# adafruit_flora_mainboard.net
KiCad netlist of a schematic drawn in EAGLE
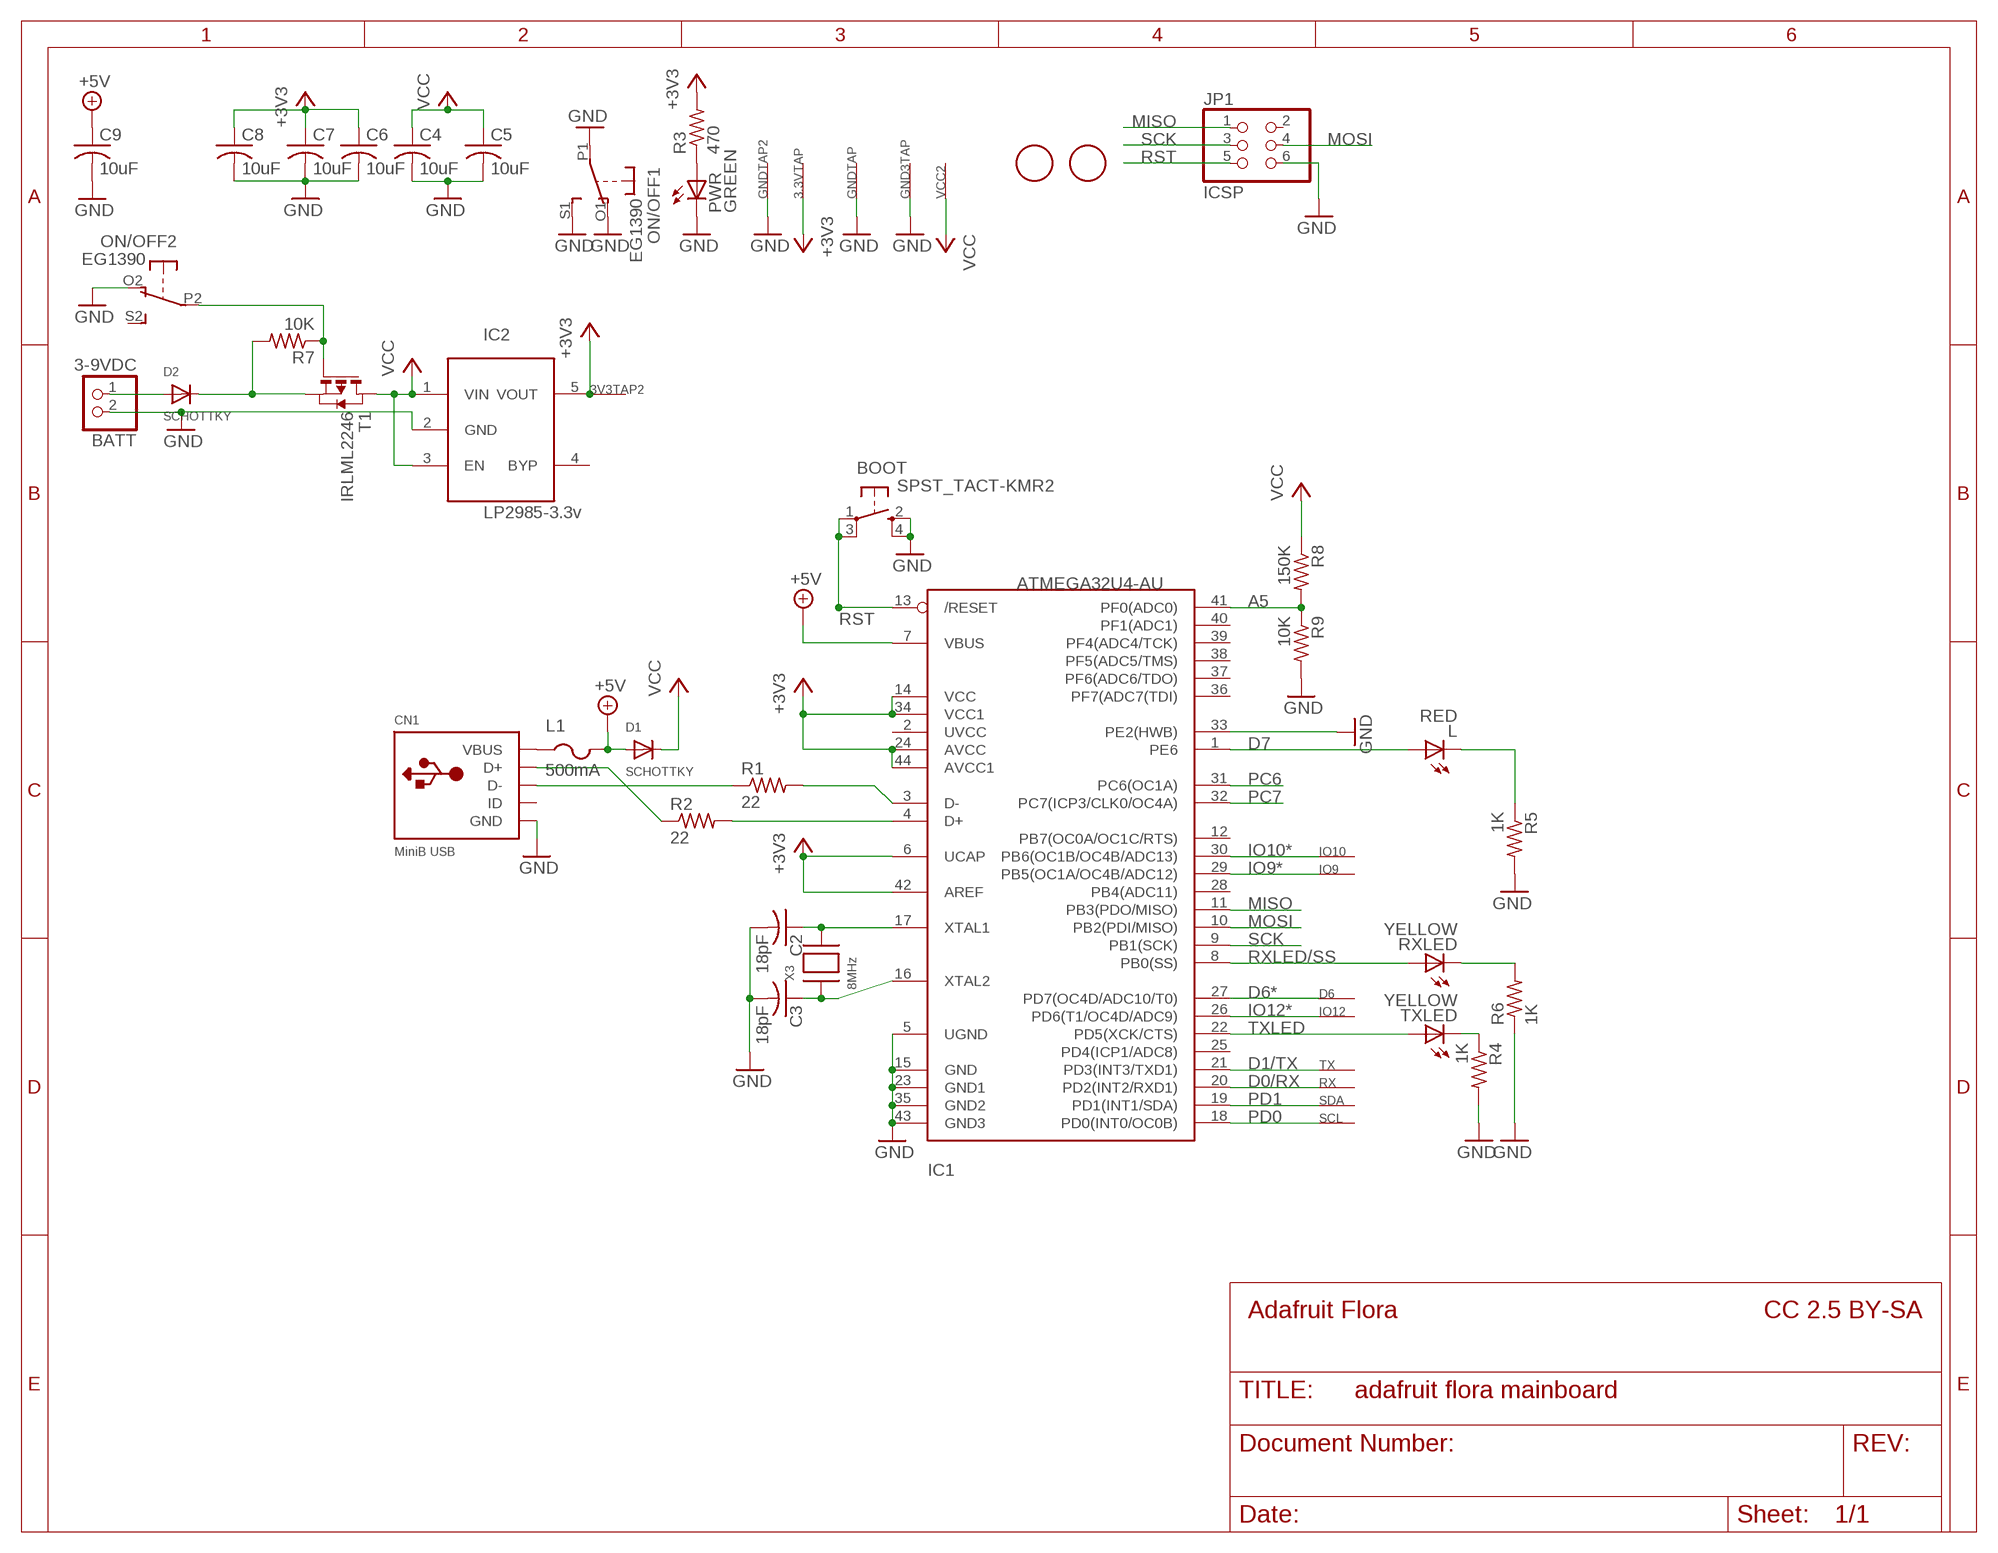
[diagram p0: schematic, sheet 1]

(export (version "E")
  (design (tool "Eeschema 10.0.6"))
  (components
    (comp (ref "3.3VTAP")
      (value "SEWTAP-2.0IN")
      (footprint "eagle-import:SEWINGTAP_2.0")
      (libsource (lib "eagle-import") (part "SEWTAP-2.0IN"))
    )
    (comp (ref "3V3TAP2")
      (value "SEWTAP-2.0IN")
      (footprint "eagle-import:SEWINGTAP_2.0")
      (libsource (lib "eagle-import") (part "SEWTAP-2.0IN"))
    )
    (comp (ref "BATT")
      (value "3-9VDC")
      (footprint "eagle-import:JST-PH-2-SMT-RA")
      (libsource (lib "eagle-import") (part "JST_2PIN-SMT-RA"))
    )
    (comp (ref "BOOT")
      (value "SPST_TACT-KMR2")
      (footprint "eagle-import:KMR2")
      (libsource (lib "eagle-import") (part "SPST_TACT-KMR2"))
    )
    (comp (ref "C2")
      (value "18pF")
      (footprint "eagle-import:C0805K")
      (libsource (lib "eagle-import") (part "C-USC0805K"))
    )
    (comp (ref "C3")
      (value "18pF")
      (footprint "eagle-import:C0805K")
      (libsource (lib "eagle-import") (part "C-USC0805K"))
    )
    (comp (ref "C4")
      (value "10uF")
      (footprint "eagle-import:C0805K")
      (libsource (lib "eagle-import") (part "C-USC0805K"))
    )
    (comp (ref "C5")
      (value "10uF")
      (footprint "eagle-import:C0805K")
      (libsource (lib "eagle-import") (part "C-USC0805K"))
    )
    (comp (ref "C6")
      (value "10uF")
      (footprint "eagle-import:C0805K")
      (libsource (lib "eagle-import") (part "C-USC0805K"))
    )
    (comp (ref "C7")
      (value "10uF")
      (footprint "eagle-import:C0805K")
      (libsource (lib "eagle-import") (part "C-USC0805K"))
    )
    (comp (ref "C8")
      (value "10uF")
      (footprint "eagle-import:C0805K")
      (libsource (lib "eagle-import") (part "C-USC0805K"))
    )
    (comp (ref "C9")
      (value "10uF")
      (footprint "eagle-import:C0805K")
      (libsource (lib "eagle-import") (part "C-USC0805K"))
    )
    (comp (ref "CN1")
      (value "MiniB USB")
      (footprint "eagle-import:USB-MINIB_LARGER")
      (libsource (lib "eagle-import") (part "USBMINIBLARGE"))
    )
    (comp (ref "D1")
      (value "SCHOTTKY")
      (footprint "eagle-import:SOD-123")
      (libsource (lib "eagle-import") (part "DIODESOD-123"))
    )
    (comp (ref "D2")
      (value "SCHOTTKY")
      (footprint "eagle-import:SOD-123")
      (libsource (lib "eagle-import") (part "DIODESOD-123"))
    )
    (comp (ref "D6")
      (value "SEWTAP-2.0IN")
      (footprint "eagle-import:SEWINGTAP_2.0")
      (libsource (lib "eagle-import") (part "SEWTAP-2.0IN"))
    )
    (comp (ref "GND3TAP")
      (value "SEWTAP-2.0IN")
      (footprint "eagle-import:SEWINGTAP_2.0")
      (libsource (lib "eagle-import") (part "SEWTAP-2.0IN"))
    )
    (comp (ref "GNDTAP")
      (value "SEWTAP-2.0IN")
      (footprint "eagle-import:SEWINGTAP_2.0")
      (libsource (lib "eagle-import") (part "SEWTAP-2.0IN"))
    )
    (comp (ref "GNDTAP2")
      (value "SEWTAP-2.0IN")
      (footprint "eagle-import:SEWINGTAP_2.0")
      (libsource (lib "eagle-import") (part "SEWTAP-2.0IN"))
    )
    (comp (ref "IC1")
      (value "ATMEGA32U4-AU")
      (footprint "eagle-import:TQFP44")
      (libsource (lib "eagle-import") (part "ATMEGA32U4-AU"))
    )
    (comp (ref "IC2")
      (value "LP2985-3.3v")
      (footprint "eagle-import:SOT23-5L")
      (libsource (lib "eagle-import") (part "LP298XS"))
    )
    (comp (ref "IO9")
      (value "SEWTAP-2.0IN")
      (footprint "eagle-import:SEWINGTAP_2.0")
      (libsource (lib "eagle-import") (part "SEWTAP-2.0IN"))
    )
    (comp (ref "IO10")
      (value "SEWTAP-2.0IN")
      (footprint "eagle-import:SEWINGTAP_2.0")
      (libsource (lib "eagle-import") (part "SEWTAP-2.0IN"))
    )
    (comp (ref "IO12")
      (value "SEWTAP-2.0IN")
      (footprint "eagle-import:SEWINGTAP_2.0")
      (libsource (lib "eagle-import") (part "SEWTAP-2.0IN"))
    )
    (comp (ref "JP1")
      (value "ICSP")
      (footprint "eagle-import:2X03")
      (libsource (lib "eagle-import") (part "PINHD-2X3"))
    )
    (comp (ref "L")
      (value "RED")
      (footprint "eagle-import:CHIPLED_0805")
      (libsource (lib "eagle-import") (part "LEDCHIPLED_0805"))
    )
    (comp (ref "L1")
      (value "500mA")
      (footprint "eagle-import:R1206")
      (libsource (lib "eagle-import") (part "PTCFUSE-1206"))
    )
    (comp (ref "ON/OFF")
      (value "EG1390")
      (footprint "eagle-import:EG1390")
      (libsource (lib "eagle-import") (part "DPDT-EG1390"))
    )
    (comp (ref "PWR")
      (value "GREEN")
      (footprint "eagle-import:CHIPLED_0805")
      (libsource (lib "eagle-import") (part "LEDCHIPLED_0805"))
    )
    (comp (ref "R1")
      (value "22")
      (footprint "eagle-import:R0805")
      (libsource (lib "eagle-import") (part "R-US_R0805"))
    )
    (comp (ref "R2")
      (value "22")
      (footprint "eagle-import:R0805")
      (libsource (lib "eagle-import") (part "R-US_R0805"))
    )
    (comp (ref "R3")
      (value "470")
      (footprint "eagle-import:R0805")
      (libsource (lib "eagle-import") (part "R-US_R0805"))
    )
    (comp (ref "R4")
      (value "1K")
      (footprint "eagle-import:R0805")
      (libsource (lib "eagle-import") (part "R-US_R0805"))
    )
    (comp (ref "R5")
      (value "1K")
      (footprint "eagle-import:R0805")
      (libsource (lib "eagle-import") (part "R-US_R0805"))
    )
    (comp (ref "R6")
      (value "1K")
      (footprint "eagle-import:R0805")
      (libsource (lib "eagle-import") (part "R-US_R0805"))
    )
    (comp (ref "R7")
      (value "10K")
      (footprint "eagle-import:R0805")
      (libsource (lib "eagle-import") (part "R-US_R0805"))
    )
    (comp (ref "R8")
      (value "150K")
      (footprint "eagle-import:R0805")
      (libsource (lib "eagle-import") (part "R-US_R0805"))
    )
    (comp (ref "R9")
      (value "10K")
      (footprint "eagle-import:R0805")
      (libsource (lib "eagle-import") (part "R-US_R0805"))
    )
    (comp (ref "RX")
      (value "SEWTAP-2.0IN")
      (footprint "eagle-import:SEWINGTAP_2.0")
      (libsource (lib "eagle-import") (part "SEWTAP-2.0IN"))
    )
    (comp (ref "RXLED")
      (value "YELLOW")
      (footprint "eagle-import:CHIPLED_0805")
      (libsource (lib "eagle-import") (part "LEDCHIPLED_0805"))
    )
    (comp (ref "SCL")
      (value "SEWTAP-2.0IN")
      (footprint "eagle-import:SEWINGTAP_2.0")
      (libsource (lib "eagle-import") (part "SEWTAP-2.0IN"))
    )
    (comp (ref "SDA")
      (value "SEWTAP-2.0IN")
      (footprint "eagle-import:SEWINGTAP_2.0")
      (libsource (lib "eagle-import") (part "SEWTAP-2.0IN"))
    )
    (comp (ref "T1")
      (value "IRLML2246")
      (footprint "eagle-import:SOT-23")
      (libsource (lib "eagle-import") (part "PMOSSOT23"))
    )
    (comp (ref "TX")
      (value "SEWTAP-2.0IN")
      (footprint "eagle-import:SEWINGTAP_2.0")
      (libsource (lib "eagle-import") (part "SEWTAP-2.0IN"))
    )
    (comp (ref "TXLED")
      (value "YELLOW")
      (footprint "eagle-import:CHIPLED_0805")
      (libsource (lib "eagle-import") (part "LEDCHIPLED_0805"))
    )
    (comp (ref "U$2")
      (value "FIDUCIAL")
      (footprint "eagle-import:FIDUCIAL_1MM")
      (libsource (lib "eagle-import") (part "FIDUCIAL"))
    )
    (comp (ref "U$6")
      (value "FIDUCIAL")
      (footprint "eagle-import:FIDUCIAL_1MM")
      (libsource (lib "eagle-import") (part "FIDUCIAL"))
    )
    (comp (ref "VCC2")
      (value "SEWTAP-2.0IN")
      (footprint "eagle-import:SEWINGTAP_2.0")
      (libsource (lib "eagle-import") (part "SEWTAP-2.0IN"))
    )
    (comp (ref "X3")
      (value "8MHz")
      (footprint "eagle-import:NX5032")
      (libsource (lib "eagle-import") (part "XTALNX5032"))
    )
  )
  (nets
    (net (code "1") (name "+3V3") (class "Default")
      (node (ref "3.3VTAP") (pin "P$1") (pinfunction "SEW_P$1") (pintype "bidirectional"))
      (node (ref "3V3TAP2") (pin "P$1") (pinfunction "SEW_P$1") (pintype "bidirectional"))
      (node (ref "C6") (pin "1") (pinfunction "1_1") (pintype "passive"))
      (node (ref "C7") (pin "1") (pinfunction "1_1") (pintype "passive"))
      (node (ref "C8") (pin "1") (pinfunction "1_1") (pintype "passive"))
      (node (ref "IC1") (pin "14") (pinfunction "VCC_14") (pintype "bidirectional"))
      (node (ref "IC1") (pin "24") (pinfunction "AVCC_24") (pintype "bidirectional"))
      (node (ref "IC1") (pin "34") (pinfunction "VCC1_34") (pintype "bidirectional"))
      (node (ref "IC1") (pin "42") (pinfunction "AREF_42") (pintype "bidirectional"))
      (node (ref "IC1") (pin "44") (pinfunction "AVCC1_44") (pintype "bidirectional"))
      (node (ref "IC1") (pin "6") (pinfunction "UCAP_6") (pintype "bidirectional"))
      (node (ref "IC2") (pin "5") (pinfunction "VOUT_5") (pintype "bidirectional"))
      (node (ref "R3") (pin "2") (pinfunction "2_2") (pintype "passive"))
    )
    (net (code "2") (name "+5V") (class "Default")
      (node (ref "C9") (pin "1") (pinfunction "1_1") (pintype "passive"))
      (node (ref "D1") (pin "A") (pinfunction "A_A") (pintype "passive"))
      (node (ref "IC1") (pin "7") (pinfunction "VBUS_7") (pintype "bidirectional"))
      (node (ref "L1") (pin "2") (pinfunction "2_2") (pintype "passive"))
    )
    (net (code "3") (name "/A5") (class "Default")
      (node (ref "IC1") (pin "41") (pinfunction "PF0(ADC0)_41") (pintype "bidirectional"))
      (node (ref "R8") (pin "2") (pinfunction "2_2") (pintype "passive"))
      (node (ref "R9") (pin "1") (pinfunction "1_1") (pintype "passive"))
    )
    (net (code "4") (name "/D0{slash}RX") (class "Default")
      (node (ref "IC1") (pin "20") (pinfunction "PD2(INT2/RXD1)_20") (pintype "bidirectional"))
      (node (ref "RX") (pin "P$1") (pinfunction "SEW_P$1") (pintype "bidirectional"))
    )
    (net (code "5") (name "/D1{slash}TX") (class "Default")
      (node (ref "IC1") (pin "21") (pinfunction "PD3(INT3/TXD1)_21") (pintype "bidirectional"))
      (node (ref "TX") (pin "P$1") (pinfunction "SEW_P$1") (pintype "bidirectional"))
    )
    (net (code "6") (name "/D6*") (class "Default")
      (node (ref "D6") (pin "P$1") (pinfunction "SEW_P$1") (pintype "bidirectional"))
      (node (ref "IC1") (pin "27") (pinfunction "PD7(OC4D/ADC10/T0)_27") (pintype "bidirectional"))
    )
    (net (code "7") (name "/D7") (class "Default")
      (node (ref "IC1") (pin "1") (pinfunction "PE6_1") (pintype "bidirectional"))
      (node (ref "L") (pin "A") (pinfunction "A_A") (pintype "passive"))
    )
    (net (code "8") (name "/IO9*") (class "Default")
      (node (ref "IC1") (pin "29") (pinfunction "PB5(OC1A/OC4B/ADC12)_29") (pintype "bidirectional"))
      (node (ref "IO9") (pin "P$1") (pinfunction "SEW_P$1") (pintype "bidirectional"))
    )
    (net (code "9") (name "/IO10*") (class "Default")
      (node (ref "IC1") (pin "30") (pinfunction "PB6(OC1B/OC4B/ADC13)_30") (pintype "bidirectional"))
      (node (ref "IO10") (pin "P$1") (pinfunction "SEW_P$1") (pintype "bidirectional"))
    )
    (net (code "10") (name "/IO12*") (class "Default")
      (node (ref "IC1") (pin "26") (pinfunction "PD6(T1/OC4D/ADC9)_26") (pintype "bidirectional"))
      (node (ref "IO12") (pin "P$1") (pinfunction "SEW_P$1") (pintype "bidirectional"))
    )
    (net (code "11") (name "/MISO") (class "Default")
      (node (ref "IC1") (pin "11") (pinfunction "PB3(PDO/MISO)_11") (pintype "bidirectional"))
      (node (ref "JP1") (pin "1") (pinfunction "1_1") (pintype "passive"))
    )
    (net (code "12") (name "/MOSI") (class "Default")
      (node (ref "IC1") (pin "10") (pinfunction "PB2(PDI/MISO)_10") (pintype "bidirectional"))
      (node (ref "JP1") (pin "4") (pinfunction "4_4") (pintype "passive"))
    )
    (net (code "13") (name "/PC6") (class "Default")
      (node (ref "IC1") (pin "31") (pinfunction "PC6(OC1A)_31") (pintype "bidirectional"))
    )
    (net (code "14") (name "/PC7") (class "Default")
      (node (ref "IC1") (pin "32") (pinfunction "PC7(ICP3/CLK0/OC4A)_32") (pintype "bidirectional"))
    )
    (net (code "15") (name "/PD0") (class "Default")
      (node (ref "IC1") (pin "18") (pinfunction "PD0(INT0/OC0B)_18") (pintype "bidirectional"))
      (node (ref "SCL") (pin "P$1") (pinfunction "SEW_P$1") (pintype "bidirectional"))
    )
    (net (code "16") (name "/PD1") (class "Default")
      (node (ref "IC1") (pin "19") (pinfunction "PD1(INT1/SDA)_19") (pintype "bidirectional"))
      (node (ref "SDA") (pin "P$1") (pinfunction "SEW_P$1") (pintype "bidirectional"))
    )
    (net (code "17") (name "/RST") (class "Default")
      (node (ref "BOOT") (pin "1") (pinfunction "P_1") (pintype "passive"))
      (node (ref "BOOT") (pin "3") (pinfunction "P1_3") (pintype "passive"))
      (node (ref "IC1") (pin "13") (pinfunction "/RESET_13") (pintype "bidirectional"))
      (node (ref "JP1") (pin "5") (pinfunction "5_5") (pintype "passive"))
    )
    (net (code "18") (name "/RXLED{slash}SS") (class "Default")
      (node (ref "IC1") (pin "8") (pinfunction "PB0(SS)_8") (pintype "bidirectional"))
      (node (ref "RXLED") (pin "A") (pinfunction "A_A") (pintype "passive"))
    )
    (net (code "19") (name "/SCK") (class "Default")
      (node (ref "IC1") (pin "9") (pinfunction "PB1(SCK)_9") (pintype "bidirectional"))
      (node (ref "JP1") (pin "3") (pinfunction "3_3") (pintype "passive"))
    )
    (net (code "20") (name "/TXLED") (class "Default")
      (node (ref "IC1") (pin "22") (pinfunction "PD5(XCK/CTS)_22") (pintype "bidirectional"))
      (node (ref "TXLED") (pin "A") (pinfunction "A_A") (pintype "passive"))
    )
    (net (code "21") (name "GND") (class "Default")
      (node (ref "BATT") (pin "2") (pinfunction "1_2") (pintype "passive"))
      (node (ref "BOOT") (pin "2") (pinfunction "S_2") (pintype "passive"))
      (node (ref "BOOT") (pin "4") (pinfunction "S1_4") (pintype "passive"))
      (node (ref "C2") (pin "2") (pinfunction "2_2") (pintype "passive"))
      (node (ref "C3") (pin "2") (pinfunction "2_2") (pintype "passive"))
      (node (ref "C4") (pin "2") (pinfunction "2_2") (pintype "passive"))
      (node (ref "C5") (pin "2") (pinfunction "2_2") (pintype "passive"))
      (node (ref "C6") (pin "2") (pinfunction "2_2") (pintype "passive"))
      (node (ref "C7") (pin "2") (pinfunction "2_2") (pintype "passive"))
      (node (ref "C8") (pin "2") (pinfunction "2_2") (pintype "passive"))
      (node (ref "C9") (pin "2") (pinfunction "2_2") (pintype "passive"))
      (node (ref "CN1") (pin "GND") (pinfunction "GND_GND") (pintype "power_in"))
      (node (ref "GND3TAP") (pin "P$1") (pinfunction "SEW_P$1") (pintype "bidirectional"))
      (node (ref "GNDTAP") (pin "P$1") (pinfunction "SEW_P$1") (pintype "bidirectional"))
      (node (ref "GNDTAP2") (pin "P$1") (pinfunction "SEW_P$1") (pintype "bidirectional"))
      (node (ref "IC1") (pin "15") (pinfunction "GND_15") (pintype "bidirectional"))
      (node (ref "IC1") (pin "23") (pinfunction "GND1_23") (pintype "bidirectional"))
      (node (ref "IC1") (pin "33") (pinfunction "PE2(HWB)_33") (pintype "bidirectional"))
      (node (ref "IC1") (pin "35") (pinfunction "GND2_35") (pintype "bidirectional"))
      (node (ref "IC1") (pin "43") (pinfunction "GND3_43") (pintype "bidirectional"))
      (node (ref "IC1") (pin "5") (pinfunction "UGND_5") (pintype "bidirectional"))
      (node (ref "IC2") (pin "2") (pinfunction "GND_2") (pintype "bidirectional"))
      (node (ref "JP1") (pin "6") (pinfunction "6_6") (pintype "passive"))
      (node (ref "ON/OFF") (pin "O1") (pinfunction "O_O1") (pintype "passive"))
      (node (ref "ON/OFF") (pin "O2") (pinfunction "O_O2") (pintype "passive"))
      (node (ref "ON/OFF") (pin "P1") (pinfunction "P_P1") (pintype "passive"))
      (node (ref "ON/OFF") (pin "S1") (pinfunction "S_S1") (pintype "passive"))
      (node (ref "PWR") (pin "C") (pinfunction "C_C") (pintype "passive"))
      (node (ref "R4") (pin "2") (pinfunction "2_2") (pintype "passive"))
      (node (ref "R5") (pin "2") (pinfunction "2_2") (pintype "passive"))
      (node (ref "R6") (pin "1") (pinfunction "1_1") (pintype "passive"))
      (node (ref "R9") (pin "2") (pinfunction "2_2") (pintype "passive"))
    )
    (net (code "22") (name "Net-(BATT-2)") (class "Default")
      (node (ref "BATT") (pin "1") (pinfunction "2_1") (pintype "passive"))
      (node (ref "D2") (pin "A") (pinfunction "A_A") (pintype "passive"))
    )
    (net (code "23") (name "Net-(CN1-PadD+)") (class "Default")
      (node (ref "CN1") (pin "D+") (pinfunction "D+_D+") (pintype "bidirectional"))
      (node (ref "R2") (pin "1") (pinfunction "1_1") (pintype "passive"))
    )
    (net (code "24") (name "Net-(CN1-PadD-)") (class "Default")
      (node (ref "CN1") (pin "D-") (pinfunction "D-_D-") (pintype "bidirectional"))
      (node (ref "R1") (pin "1") (pinfunction "1_1") (pintype "passive"))
    )
    (net (code "25") (name "Net-(CN1-PadVBUS)") (class "Default")
      (node (ref "CN1") (pin "VBUS") (pinfunction "VBUS_VBUS") (pintype "power_in"))
      (node (ref "L1") (pin "1") (pinfunction "1_1") (pintype "passive"))
    )
    (net (code "26") (name "Net-(IC1-D+)") (class "Default")
      (node (ref "IC1") (pin "4") (pinfunction "D+_4") (pintype "bidirectional"))
      (node (ref "R2") (pin "2") (pinfunction "2_2") (pintype "passive"))
    )
    (net (code "27") (name "Net-(IC1-D-)") (class "Default")
      (node (ref "IC1") (pin "3") (pinfunction "D-_3") (pintype "bidirectional"))
      (node (ref "R1") (pin "2") (pinfunction "2_2") (pintype "passive"))
    )
    (net (code "28") (name "Net-(IC1-XTAL1)") (class "Default")
      (node (ref "C2") (pin "1") (pinfunction "1_1") (pintype "passive"))
      (node (ref "IC1") (pin "17") (pinfunction "XTAL1_17") (pintype "bidirectional"))
      (node (ref "X3") (pin "P$2") (pinfunction "P$2_P$2") (pintype "bidirectional"))
    )
    (net (code "29") (name "Net-(IC1-XTAL2)") (class "Default")
      (node (ref "C3") (pin "1") (pinfunction "1_1") (pintype "passive"))
      (node (ref "IC1") (pin "16") (pinfunction "XTAL2_16") (pintype "bidirectional"))
      (node (ref "X3") (pin "P$1") (pinfunction "P$1_P$1") (pintype "bidirectional"))
    )
    (net (code "30") (name "Net-(L-PadC)") (class "Default")
      (node (ref "L") (pin "C") (pinfunction "C_C") (pintype "passive"))
      (node (ref "R5") (pin "1") (pinfunction "1_1") (pintype "passive"))
    )
    (net (code "31") (name "Net-(ON/OFFB-P)") (class "Default")
      (node (ref "ON/OFF") (pin "P2") (pinfunction "P_P2") (pintype "passive"))
      (node (ref "R7") (pin "1") (pinfunction "1_1") (pintype "passive"))
      (node (ref "T1") (pin "3") (pinfunction "G_3") (pintype "passive"))
    )
    (net (code "32") (name "Net-(PWR-PadA)") (class "Default")
      (node (ref "PWR") (pin "A") (pinfunction "A_A") (pintype "passive"))
      (node (ref "R3") (pin "1") (pinfunction "1_1") (pintype "passive"))
    )
    (net (code "33") (name "Net-(R4-Pad1)") (class "Default")
      (node (ref "R4") (pin "1") (pinfunction "1_1") (pintype "passive"))
      (node (ref "TXLED") (pin "C") (pinfunction "C_C") (pintype "passive"))
    )
    (net (code "34") (name "Net-(R6-Pad2)") (class "Default")
      (node (ref "R6") (pin "2") (pinfunction "2_2") (pintype "passive"))
      (node (ref "RXLED") (pin "C") (pinfunction "C_C") (pintype "passive"))
    )
    (net (code "35") (name "Net-(T1-S)") (class "Default")
      (node (ref "D2") (pin "C") (pinfunction "C_C") (pintype "passive"))
      (node (ref "R7") (pin "2") (pinfunction "2_2") (pintype "passive"))
      (node (ref "T1") (pin "2") (pinfunction "S_2") (pintype "passive"))
    )
    (net (code "36") (name "VCC") (class "Default")
      (node (ref "C4") (pin "1") (pinfunction "1_1") (pintype "passive"))
      (node (ref "C5") (pin "1") (pinfunction "1_1") (pintype "passive"))
      (node (ref "D1") (pin "C") (pinfunction "C_C") (pintype "passive"))
      (node (ref "IC2") (pin "1") (pinfunction "VIN_1") (pintype "bidirectional"))
      (node (ref "IC2") (pin "3") (pinfunction "EN_3") (pintype "bidirectional"))
      (node (ref "R8") (pin "1") (pinfunction "1_1") (pintype "passive"))
      (node (ref "T1") (pin "1") (pinfunction "D_1") (pintype "passive"))
      (node (ref "VCC2") (pin "P$1") (pinfunction "SEW_P$1") (pintype "bidirectional"))
    )
    (net (code "37") (name "unconnected-(CN1-PadID)") (class "Default")
      (node (ref "CN1") (pin "ID") (pinfunction "ID_ID") (pintype "bidirectional"))
    )
    (net (code "38") (name "unconnected-(IC1-PB4(ADC11)-Pad28)") (class "Default")
      (node (ref "IC1") (pin "28") (pinfunction "PB4(ADC11)_28") (pintype "bidirectional"))
    )
    (net (code "39") (name "unconnected-(IC1-PB7(OC0A{slash}OC1C{slash}RTS)-Pad12)") (class "Default")
      (node (ref "IC1") (pin "12") (pinfunction "PB7(OC0A/OC1C/RTS)_12") (pintype "bidirectional"))
    )
    (net (code "40") (name "unconnected-(IC1-PD4(ICP1{slash}ADC8)-Pad25)") (class "Default")
      (node (ref "IC1") (pin "25") (pinfunction "PD4(ICP1/ADC8)_25") (pintype "bidirectional"))
    )
    (net (code "41") (name "unconnected-(IC1-PF1(ADC1)-Pad40)") (class "Default")
      (node (ref "IC1") (pin "40") (pinfunction "PF1(ADC1)_40") (pintype "bidirectional"))
    )
    (net (code "42") (name "unconnected-(IC1-PF4(ADC4{slash}TCK)-Pad39)") (class "Default")
      (node (ref "IC1") (pin "39") (pinfunction "PF4(ADC4/TCK)_39") (pintype "bidirectional"))
    )
    (net (code "43") (name "unconnected-(IC1-PF5(ADC5{slash}TMS)-Pad38)") (class "Default")
      (node (ref "IC1") (pin "38") (pinfunction "PF5(ADC5/TMS)_38") (pintype "bidirectional"))
    )
    (net (code "44") (name "unconnected-(IC1-PF6(ADC6{slash}TDO)-Pad37)") (class "Default")
      (node (ref "IC1") (pin "37") (pinfunction "PF6(ADC6/TDO)_37") (pintype "bidirectional"))
    )
    (net (code "45") (name "unconnected-(IC1-PF7(ADC7(TDI)-Pad36)") (class "Default")
      (node (ref "IC1") (pin "36") (pinfunction "PF7(ADC7(TDI)_36") (pintype "bidirectional"))
    )
    (net (code "46") (name "unconnected-(IC1-UVCC-Pad2)") (class "Default")
      (node (ref "IC1") (pin "2") (pinfunction "UVCC_2") (pintype "bidirectional"))
    )
    (net (code "47") (name "unconnected-(IC2-BYP-Pad4)") (class "Default")
      (node (ref "IC2") (pin "4") (pinfunction "BYP_4") (pintype "bidirectional"))
    )
    (net (code "48") (name "unconnected-(JP1-Pad2)") (class "Default")
      (node (ref "JP1") (pin "2") (pinfunction "2_2") (pintype "passive"))
    )
    (net (code "49") (name "unconnected-(ON/OFFB-S-PadS2)") (class "Default")
      (node (ref "ON/OFF") (pin "S2") (pinfunction "S_S2") (pintype "passive"))
    )
  )
)
